# Output_Devices.net
KiCad netlist of a schematic drawn in Altium Designer
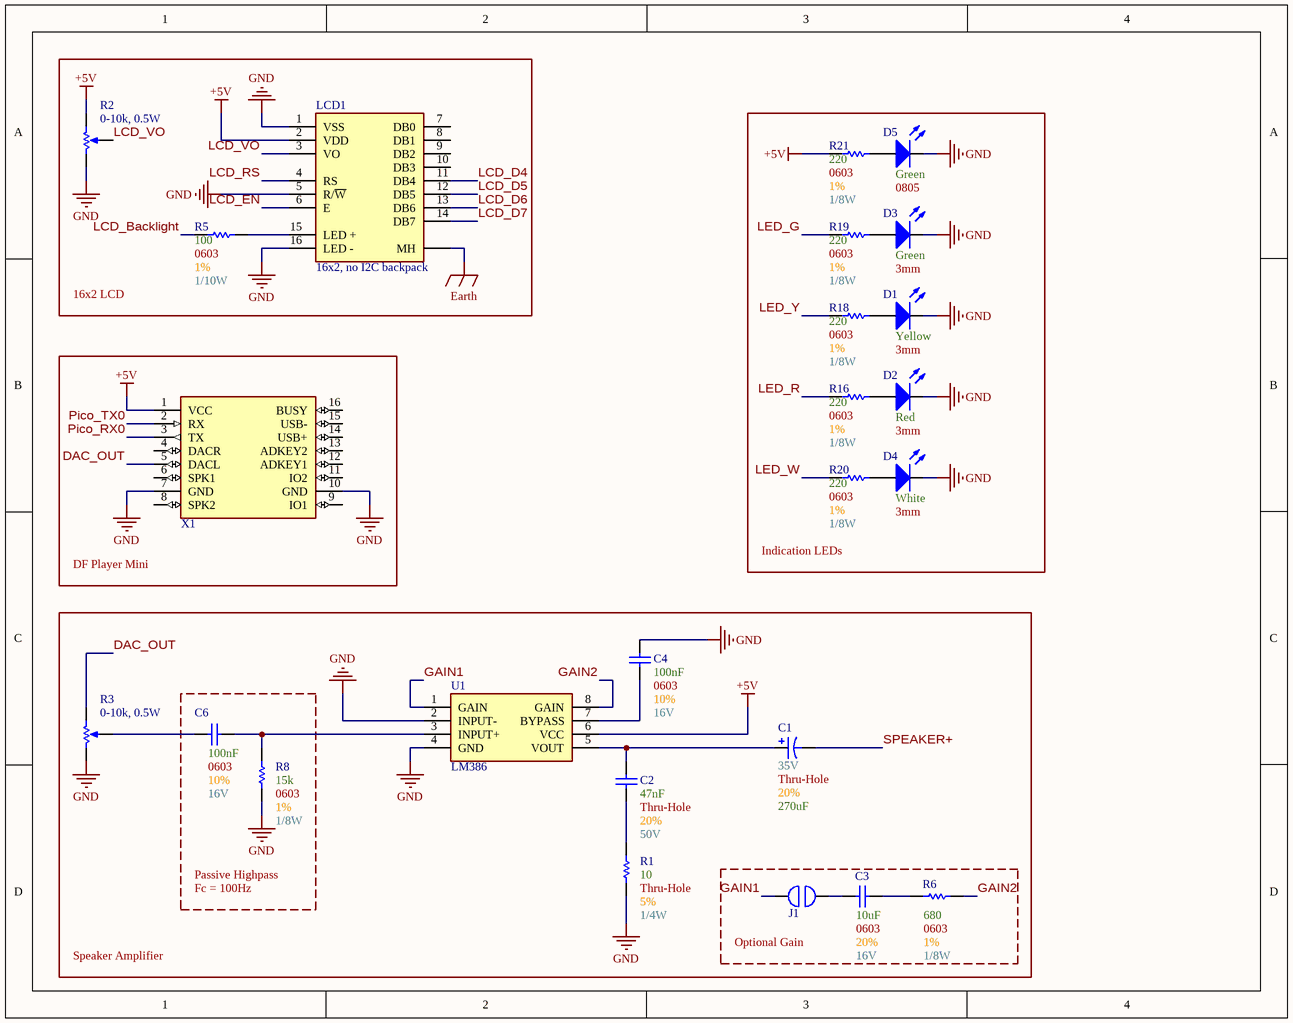
[diagram p0: Output Devices.SchDoc]

(export (version "E")
  (design (tool "Eeschema 10.0.6"))
  (components
    (comp (ref "C1")
      (value "[Cap] Thru-Hole 270uF 20% 35V")
      (footprint "[Cap] Thru-Hole Polarized 8mm")
      (description "35ZLH270MEFC8X16")
      (fields
        (field (name "MAX VOLTAGE") "35V")
        (field (name "SIZE PACKAGE") "Thru-Hole")
        (field (name "TOLERANCE") "20%")
        (field (name "CAPACITANCE") "270uF")
      )
      (libsource (lib "Capacitors") (part "[Cap] Thru-Hole 270uF 20% 35V"))
    )
    (comp (ref "C2")
      (value "[Cap] Thru-Hole 47nF 20% 50V")
      (footprint "[Cap] Thru-Hole Nonpolarized Ceramic")
      (description "C317C473M5U5TA")
      (fields
        (field (name "MAX VOLTAGE") "50V")
        (field (name "SIZE PACKAGE") "Thru-Hole")
        (field (name "TOLERANCE") "20%")
        (field (name "CAPACITANCE") "47nF")
      )
      (libsource (lib "Capacitors") (part "[Cap] Thru-Hole 47nF 20% 50V"))
    )
    (comp (ref "C3")
      (value "[Cap] 0603 10uF 20% 16V")
      (footprint "[Cap] SMD 0603")
      (description "GRM188C81C106MA73D")
      (fields
        (field (name "MAX VOLTAGE") "16V")
        (field (name "SIZE PACKAGE") "0603")
        (field (name "TOLERANCE") "20%")
        (field (name "CAPACITANCE") "10uF")
      )
      (libsource (lib "Capacitors") (part "[Cap] 0603 10uF 20% 16V"))
    )
    (comp (ref "C4")
      (value "[Cap] 0603 0.1uF 10% 16V")
      (footprint "[Cap] SMD 0603")
      (description "CC0603KRX7R7BB104")
      (fields
        (field (name "MAX VOLTAGE") "16V")
        (field (name "SIZE PACKAGE") "0603")
        (field (name "TOLERANCE") "10%")
        (field (name "CAPACITANCE") "100nF")
      )
      (libsource (lib "Capacitors") (part "[Cap] 0603 0.1uF 10% 16V"))
    )
    (comp (ref "C6")
      (value "[Cap] 0603 0.1uF 10% 16V")
      (footprint "[Cap] SMD 0603")
      (description "CC0603KRX7R7BB104")
      (fields
        (field (name "MAX VOLTAGE") "16V")
        (field (name "SIZE PACKAGE") "0603")
        (field (name "TOLERANCE") "10%")
        (field (name "CAPACITANCE") "100nF")
      )
      (libsource (lib "Capacitors") (part "[Cap] 0603 0.1uF 10% 16V"))
    )
    (comp (ref "D1")
      (value "[LED] Thru-Hole 3mm Yellow")
      (footprint "[LED] Thru-Hole 3mm Yellow")
      (description "151031YS05900")
      (fields (field (name "COLOR") "Yellow") (field (name "LENS DIAMETER") "3mm"))
      (libsource (lib "LEDs") (part "[LED] Thru-Hole 3mm Yellow"))
    )
    (comp (ref "D2")
      (value "[LED] Thru-Hole 3mm Red")
      (footprint "[LED] Thru-Hole 3mm Red")
      (description "151031SS06000")
      (fields (field (name "COLOR") "Red") (field (name "LENS DIAMETER") "3mm"))
      (libsource (lib "LEDs") (part "[LED] Thru-Hole 3mm Red"))
    )
    (comp (ref "D3")
      (value "[LED] Thru-Hole 3mm Green")
      (footprint "[LED] Thru-Hole 3mm Green")
      (description "151031VS06000")
      (fields (field (name "COLOR") "Green") (field (name "LENS DIAMETER") "3mm"))
      (libsource (lib "LEDs") (part "[LED] Thru-Hole 3mm Green"))
    )
    (comp (ref "D4")
      (value "[LED] Thru-Hole 3mm White")
      (footprint "[LED] Thru-Hole 3mm White")
      (description "151031VS06000")
      (fields (field (name "COLOR") "White") (field (name "LENS DIAMETER") "3mm"))
      (libsource (lib "LEDs") (part "[LED] Thru-Hole 3mm White"))
    )
    (comp (ref "D5")
      (value "[LED] SMD 0805 Green")
      (footprint "[LED] SMD 0805")
      (description "LG R971-KN-1-0-20-R18")
      (fields (field (name "COLOR") "Green") (field (name "SIZE PACKAGE") "0805"))
      (libsource (lib "LEDs") (part "[LED] SMD 0805 Green"))
    )
    (comp (ref "J1")
      (value "[Jumper] Thru-Hole 2pin")
      (footprint "[Jumper] Thru-Hole 2pin")
      (libsource (lib "Misc Components") (part "[Jumper] Thru-Hole 2pin"))
    )
    (comp (ref "LCD1")
      (value "16x2, no I2C backpack")
      (footprint "[LCD] 16x2 Parallel")
      (description "Sunfounder")
      (libsource (lib "Devices") (part "[LCD] 16x2 Parallel"))
    )
    (comp (ref "R1")
      (value "[10] Thru-Hole 5% 1/4W")
      (footprint "[Res] Thru-Hole 1/4W")
      (description "CFR-25JT-52-10R")
      (fields
        (field (name "SIZE PACKAGE") "Thru-Hole")
        (field (name "WATTAGE") "1/4W")
        (field (name "TOLERANCE") "5%")
        (field (name "RESISTANCE") "10")
      )
      (libsource (lib "Resistors") (part "[10] Thru-Hole 5% 1/4W"))
    )
    (comp (ref "R2")
      (value "0-10k, 0.5W")
      (footprint "[Potentiometer] 10k 0.5W (2)")
      (description "3386T-1-103LF")
      (libsource (lib "Misc Components") (part "[Potentiometer] 10k 0.5W"))
    )
    (comp (ref "R3")
      (value "0-10k, 0.5W")
      (footprint "[Potentiometer] 10k 0.5W (2)")
      (description "3386T-1-103LF")
      (libsource (lib "Misc Components") (part "[Potentiometer] 10k 0.5W"))
    )
    (comp (ref "R5")
      (value "[100] SMD 0603 1% 1/10W")
      (footprint "[Res] SMD 0603")
      (description "RC0603FR-07100RL")
      (fields
        (field (name "WATTAGE") "1/10W")
        (field (name "TOLERANCE") "1%")
        (field (name "RESISTANCE") "100")
        (field (name "SIZE PACKAGE") "0603")
      )
      (libsource (lib "Resistors") (part "[100] SMD 0603 1% 1/10W"))
    )
    (comp (ref "R6")
      (value "[680] SMD 0603 1% 1/8W")
      (footprint "[Res] SMD 0603")
      (description "CRCW0603680RFKEA")
      (fields
        (field (name "WATTAGE") "1/8W")
        (field (name "TOLERANCE") "1%")
        (field (name "RESISTANCE") "680")
        (field (name "SIZE PACKAGE") "0603")
      )
      (libsource (lib "Resistors") (part "[680] SMD 0603 1% 1/8W"))
    )
    (comp (ref "R8")
      (value "[15k] SMD 0603 1% 1/8W")
      (footprint "[Res] SMD 0603")
      (description "CRCW060315K0FKEA")
      (fields
        (field (name "WATTAGE") "1/8W")
        (field (name "TOLERANCE") "1%")
        (field (name "RESISTANCE") "15k")
        (field (name "SIZE PACKAGE") "0603")
      )
      (libsource (lib "Resistors") (part "[15k] SMD 0603 1% 1/8W"))
    )
    (comp (ref "R16")
      (value "[220] SMD 0603 1% 1/10W")
      (footprint "[Res] SMD 0603")
      (description "CRGCQ0805F220R")
      (fields
        (field (name "WATTAGE") "1/8W")
        (field (name "TOLERANCE") "1%")
        (field (name "RESISTANCE") "220")
        (field (name "SIZE PACKAGE") "0603")
      )
      (libsource (lib "Resistors") (part "[220] SMD 0603 1% 1/10W"))
    )
    (comp (ref "R18")
      (value "[220] SMD 0603 1% 1/10W")
      (footprint "[Res] SMD 0603")
      (description "CRGCQ0805F220R")
      (fields
        (field (name "WATTAGE") "1/8W")
        (field (name "TOLERANCE") "1%")
        (field (name "RESISTANCE") "220")
        (field (name "SIZE PACKAGE") "0603")
      )
      (libsource (lib "Resistors") (part "[220] SMD 0603 1% 1/10W"))
    )
    (comp (ref "R19")
      (value "[220] SMD 0603 1% 1/10W")
      (footprint "[Res] SMD 0603")
      (description "CRGCQ0805F220R")
      (fields
        (field (name "WATTAGE") "1/8W")
        (field (name "TOLERANCE") "1%")
        (field (name "RESISTANCE") "220")
        (field (name "SIZE PACKAGE") "0603")
      )
      (libsource (lib "Resistors") (part "[220] SMD 0603 1% 1/10W"))
    )
    (comp (ref "R20")
      (value "[220] SMD 0603 1% 1/10W")
      (footprint "[Res] SMD 0603")
      (description "CRGCQ0805F220R")
      (fields
        (field (name "WATTAGE") "1/8W")
        (field (name "TOLERANCE") "1%")
        (field (name "RESISTANCE") "220")
        (field (name "SIZE PACKAGE") "0603")
      )
      (libsource (lib "Resistors") (part "[220] SMD 0603 1% 1/10W"))
    )
    (comp (ref "R21")
      (value "[220] SMD 0603 1% 1/10W")
      (footprint "[Res] SMD 0603")
      (description "CRGCQ0805F220R")
      (fields
        (field (name "WATTAGE") "1/8W")
        (field (name "TOLERANCE") "1%")
        (field (name "RESISTANCE") "220")
        (field (name "SIZE PACKAGE") "0603")
      )
      (libsource (lib "Resistors") (part "[220] SMD 0603 1% 1/10W"))
    )
    (comp (ref "U1")
      (value "LM386")
      (footprint "[Amp] LM386")
      (description "LM386N-1/NOPB")
      (libsource (lib "ICs") (part "[Amp] LM386"))
    )
    (comp (ref "X1")
      (value "[MP3] DFPlayer Mini MP3 Player")
      (footprint "[MP3] DFPlayer Mini MP3 Player")
      (description "DFR0299")
      (libsource (lib "Devices") (part "[MP3] DFPlayer Mini MP3 Player"))
    )
  )
  (nets
    (net (code "1") (name "+5V") (class "Default")
      (node (ref "LCD1") (pin "2") (pinfunction "VDD_2") (pintype "passive"))
      (node (ref "R2") (pin "1") (pinfunction "TOP_1") (pintype "passive"))
      (node (ref "R21") (pin "1") (pinfunction "1_1") (pintype "passive"))
      (node (ref "U1") (pin "6") (pinfunction "VCC_6") (pintype "passive"))
      (node (ref "X1") (pin "1") (pinfunction "VCC_1") (pintype "power_in"))
    )
    (net (code "2") (name "/DAC_OUT") (class "Default")
      (node (ref "R3") (pin "1") (pinfunction "TOP_1") (pintype "passive"))
      (node (ref "X1") (pin "5") (pinfunction "DACL_5") (pintype "bidirectional"))
    )
    (net (code "3") (name "/GAIN1") (class "Default")
      (node (ref "J1") (pin "1") (pintype "passive"))
      (node (ref "U1") (pin "1") (pinfunction "GAIN_1") (pintype "passive"))
    )
    (net (code "4") (name "/GAIN2") (class "Default")
      (node (ref "R6") (pin "2") (pinfunction "2_2") (pintype "passive"))
      (node (ref "U1") (pin "8") (pinfunction "GAIN_8") (pintype "passive"))
    )
    (net (code "5") (name "/LCD_Backlight") (class "Default")
      (node (ref "R5") (pin "1") (pinfunction "1_1") (pintype "passive"))
    )
    (net (code "6") (name "/LCD_D4") (class "Default")
      (node (ref "LCD1") (pin "11") (pinfunction "DB4_11") (pintype "passive"))
    )
    (net (code "7") (name "/LCD_D5") (class "Default")
      (node (ref "LCD1") (pin "12") (pinfunction "DB5_12") (pintype "passive"))
    )
    (net (code "8") (name "/LCD_D6") (class "Default")
      (node (ref "LCD1") (pin "13") (pinfunction "DB6_13") (pintype "passive"))
    )
    (net (code "9") (name "/LCD_D7") (class "Default")
      (node (ref "LCD1") (pin "14") (pinfunction "DB7_14") (pintype "passive"))
    )
    (net (code "10") (name "/LCD_EN") (class "Default")
      (node (ref "LCD1") (pin "6") (pinfunction "E_6") (pintype "passive"))
    )
    (net (code "11") (name "/LCD_RS") (class "Default")
      (node (ref "LCD1") (pin "4") (pinfunction "RS_4") (pintype "passive"))
    )
    (net (code "12") (name "/LCD_VO") (class "Default")
      (node (ref "LCD1") (pin "3") (pinfunction "VO_3") (pintype "passive"))
      (node (ref "R2") (pin "2") (pinfunction "TAP_2") (pintype "passive"))
    )
    (net (code "13") (name "/LED_G") (class "Default")
      (node (ref "R19") (pin "1") (pinfunction "1_1") (pintype "passive"))
    )
    (net (code "14") (name "/LED_R") (class "Default")
      (node (ref "R16") (pin "1") (pinfunction "1_1") (pintype "passive"))
    )
    (net (code "15") (name "/LED_W") (class "Default")
      (node (ref "R20") (pin "1") (pinfunction "1_1") (pintype "passive"))
    )
    (net (code "16") (name "/LED_Y") (class "Default")
      (node (ref "R18") (pin "1") (pinfunction "1_1") (pintype "passive"))
    )
    (net (code "17") (name "/Pico_RX0") (class "Default")
      (node (ref "X1") (pin "3") (pinfunction "TX_3") (pintype "output"))
    )
    (net (code "18") (name "/Pico_TX0") (class "Default")
      (node (ref "X1") (pin "2") (pinfunction "RX_2") (pintype "input"))
    )
    (net (code "19") (name "/SPEAKER+") (class "Default")
      (node (ref "C1") (pin "2") (pinfunction "2_2") (pintype "passive"))
    )
    (net (code "20") (name "Earth") (class "Default")
      (node (ref "LCD1") (pin "MH") (pinfunction "MH_MH") (pintype "passive"))
    )
    (net (code "21") (name "GND") (class "Default")
      (node (ref "C4") (pin "2") (pinfunction "2_2") (pintype "passive"))
      (node (ref "D1") (pin "2") (pinfunction "Cathode_2") (pintype "passive"))
      (node (ref "D2") (pin "2") (pinfunction "Cathode_2") (pintype "passive"))
      (node (ref "D3") (pin "2") (pinfunction "Cathode_2") (pintype "passive"))
      (node (ref "D4") (pin "2") (pinfunction "Cathode_2") (pintype "passive"))
      (node (ref "D5") (pin "2") (pinfunction "Cathode_2") (pintype "passive"))
      (node (ref "LCD1") (pin "1") (pinfunction "VSS_1") (pintype "passive"))
      (node (ref "LCD1") (pin "16") (pinfunction "LED_-_16") (pintype "passive"))
      (node (ref "LCD1") (pin "5") (pinfunction "R/~{W}_5") (pintype "passive"))
      (node (ref "R1") (pin "1") (pinfunction "1_1") (pintype "passive"))
      (node (ref "R2") (pin "3") (pinfunction "BOT_3") (pintype "passive"))
      (node (ref "R3") (pin "3") (pinfunction "BOT_3") (pintype "passive"))
      (node (ref "R8") (pin "1") (pinfunction "1_1") (pintype "passive"))
      (node (ref "U1") (pin "2") (pinfunction "INPUT-_2") (pintype "passive"))
      (node (ref "U1") (pin "4") (pinfunction "GND_4") (pintype "passive"))
      (node (ref "X1") (pin "10") (pinfunction "GND_10") (pintype "power_in"))
      (node (ref "X1") (pin "7") (pinfunction "GND_7") (pintype "power_in"))
    )
    (net (code "22") (name "Net-(C2-Pad1)") (class "Default")
      (node (ref "C2") (pin "1") (pinfunction "1_1") (pintype "passive"))
      (node (ref "R1") (pin "2") (pinfunction "2_2") (pintype "passive"))
    )
    (net (code "23") (name "Net-(C3-Pad1)") (class "Default")
      (node (ref "C3") (pin "1") (pinfunction "1_1") (pintype "passive"))
      (node (ref "J1") (pin "2") (pintype "passive"))
    )
    (net (code "24") (name "Net-(C3-Pad2)") (class "Default")
      (node (ref "C3") (pin "2") (pinfunction "2_2") (pintype "passive"))
      (node (ref "R6") (pin "1") (pinfunction "1_1") (pintype "passive"))
    )
    (net (code "25") (name "Net-(D1-Anode)") (class "Default")
      (node (ref "D1") (pin "1") (pinfunction "Anode_1") (pintype "passive"))
      (node (ref "R18") (pin "2") (pinfunction "2_2") (pintype "passive"))
    )
    (net (code "26") (name "Net-(D2-Anode)") (class "Default")
      (node (ref "D2") (pin "1") (pinfunction "Anode_1") (pintype "passive"))
      (node (ref "R16") (pin "2") (pinfunction "2_2") (pintype "passive"))
    )
    (net (code "27") (name "Net-(D3-Anode)") (class "Default")
      (node (ref "D3") (pin "1") (pinfunction "Anode_1") (pintype "passive"))
      (node (ref "R19") (pin "2") (pinfunction "2_2") (pintype "passive"))
    )
    (net (code "28") (name "Net-(D4-Anode)") (class "Default")
      (node (ref "D4") (pin "1") (pinfunction "Anode_1") (pintype "passive"))
      (node (ref "R20") (pin "2") (pinfunction "2_2") (pintype "passive"))
    )
    (net (code "29") (name "Net-(D5-Anode)") (class "Default")
      (node (ref "D5") (pin "1") (pinfunction "Anode_1") (pintype "passive"))
      (node (ref "R21") (pin "2") (pinfunction "2_2") (pintype "passive"))
    )
    (net (code "30") (name "Net-(LCD1-LED_+)") (class "Default")
      (node (ref "LCD1") (pin "15") (pinfunction "LED_+_15") (pintype "passive"))
      (node (ref "R5") (pin "2") (pinfunction "2_2") (pintype "passive"))
    )
    (net (code "31") (name "Net-(R3-TAP)") (class "Default")
      (node (ref "C6") (pin "2") (pinfunction "2_2") (pintype "passive"))
      (node (ref "R3") (pin "2") (pinfunction "TAP_2") (pintype "passive"))
    )
    (net (code "32") (name "Net-(U1-BYPASS)") (class "Default")
      (node (ref "C4") (pin "1") (pinfunction "1_1") (pintype "passive"))
      (node (ref "U1") (pin "7") (pinfunction "BYPASS_7") (pintype "passive"))
    )
    (net (code "33") (name "Net-(U1-INPUT+)") (class "Default")
      (node (ref "C6") (pin "1") (pinfunction "1_1") (pintype "passive"))
      (node (ref "R8") (pin "2") (pinfunction "2_2") (pintype "passive"))
      (node (ref "U1") (pin "3") (pinfunction "INPUT+_3") (pintype "passive"))
    )
    (net (code "34") (name "Net-(U1-VOUT)") (class "Default")
      (node (ref "C1") (pin "1") (pinfunction "1_1") (pintype "passive"))
      (node (ref "C2") (pin "2") (pinfunction "2_2") (pintype "passive"))
      (node (ref "U1") (pin "5") (pinfunction "VOUT_5") (pintype "passive"))
    )
    (net (code "35") (name "unconnected-(LCD1-DB0-Pad7)") (class "Default")
      (node (ref "LCD1") (pin "7") (pinfunction "DB0_7") (pintype "passive"))
    )
    (net (code "36") (name "unconnected-(LCD1-DB1-Pad8)") (class "Default")
      (node (ref "LCD1") (pin "8") (pinfunction "DB1_8") (pintype "passive"))
    )
    (net (code "37") (name "unconnected-(LCD1-DB2-Pad9)") (class "Default")
      (node (ref "LCD1") (pin "9") (pinfunction "DB2_9") (pintype "passive"))
    )
    (net (code "38") (name "unconnected-(LCD1-DB3-Pad10)") (class "Default")
      (node (ref "LCD1") (pin "10") (pinfunction "DB3_10") (pintype "passive"))
    )
    (net (code "39") (name "unconnected-(X1-ADKEY1-Pad12)") (class "Default")
      (node (ref "X1") (pin "12") (pinfunction "ADKEY1_12") (pintype "bidirectional"))
    )
    (net (code "40") (name "unconnected-(X1-ADKEY2-Pad13)") (class "Default")
      (node (ref "X1") (pin "13") (pinfunction "ADKEY2_13") (pintype "bidirectional"))
    )
    (net (code "41") (name "unconnected-(X1-BUSY-Pad16)") (class "Default")
      (node (ref "X1") (pin "16") (pinfunction "BUSY_16") (pintype "bidirectional"))
    )
    (net (code "42") (name "unconnected-(X1-DACR-Pad4)") (class "Default")
      (node (ref "X1") (pin "4") (pinfunction "DACR_4") (pintype "bidirectional"))
    )
    (net (code "43") (name "unconnected-(X1-IO1-Pad9)") (class "Default")
      (node (ref "X1") (pin "9") (pinfunction "IO1_9") (pintype "bidirectional"))
    )
    (net (code "44") (name "unconnected-(X1-IO2-Pad11)") (class "Default")
      (node (ref "X1") (pin "11") (pinfunction "IO2_11") (pintype "bidirectional"))
    )
    (net (code "45") (name "unconnected-(X1-SPK1-Pad6)") (class "Default")
      (node (ref "X1") (pin "6") (pinfunction "SPK1_6") (pintype "bidirectional"))
    )
    (net (code "46") (name "unconnected-(X1-SPK2-Pad8)") (class "Default")
      (node (ref "X1") (pin "8") (pinfunction "SPK2_8") (pintype "bidirectional"))
    )
    (net (code "47") (name "unconnected-(X1-USB+-Pad14)") (class "Default")
      (node (ref "X1") (pin "14") (pinfunction "USB+_14") (pintype "bidirectional"))
    )
    (net (code "48") (name "unconnected-(X1-USB--Pad15)") (class "Default")
      (node (ref "X1") (pin "15") (pinfunction "USB-_15") (pintype "bidirectional"))
    )
  )
)
